# debugging_board_3_H-bridges.net
KiCad netlist of a schematic drawn in Altium Designer
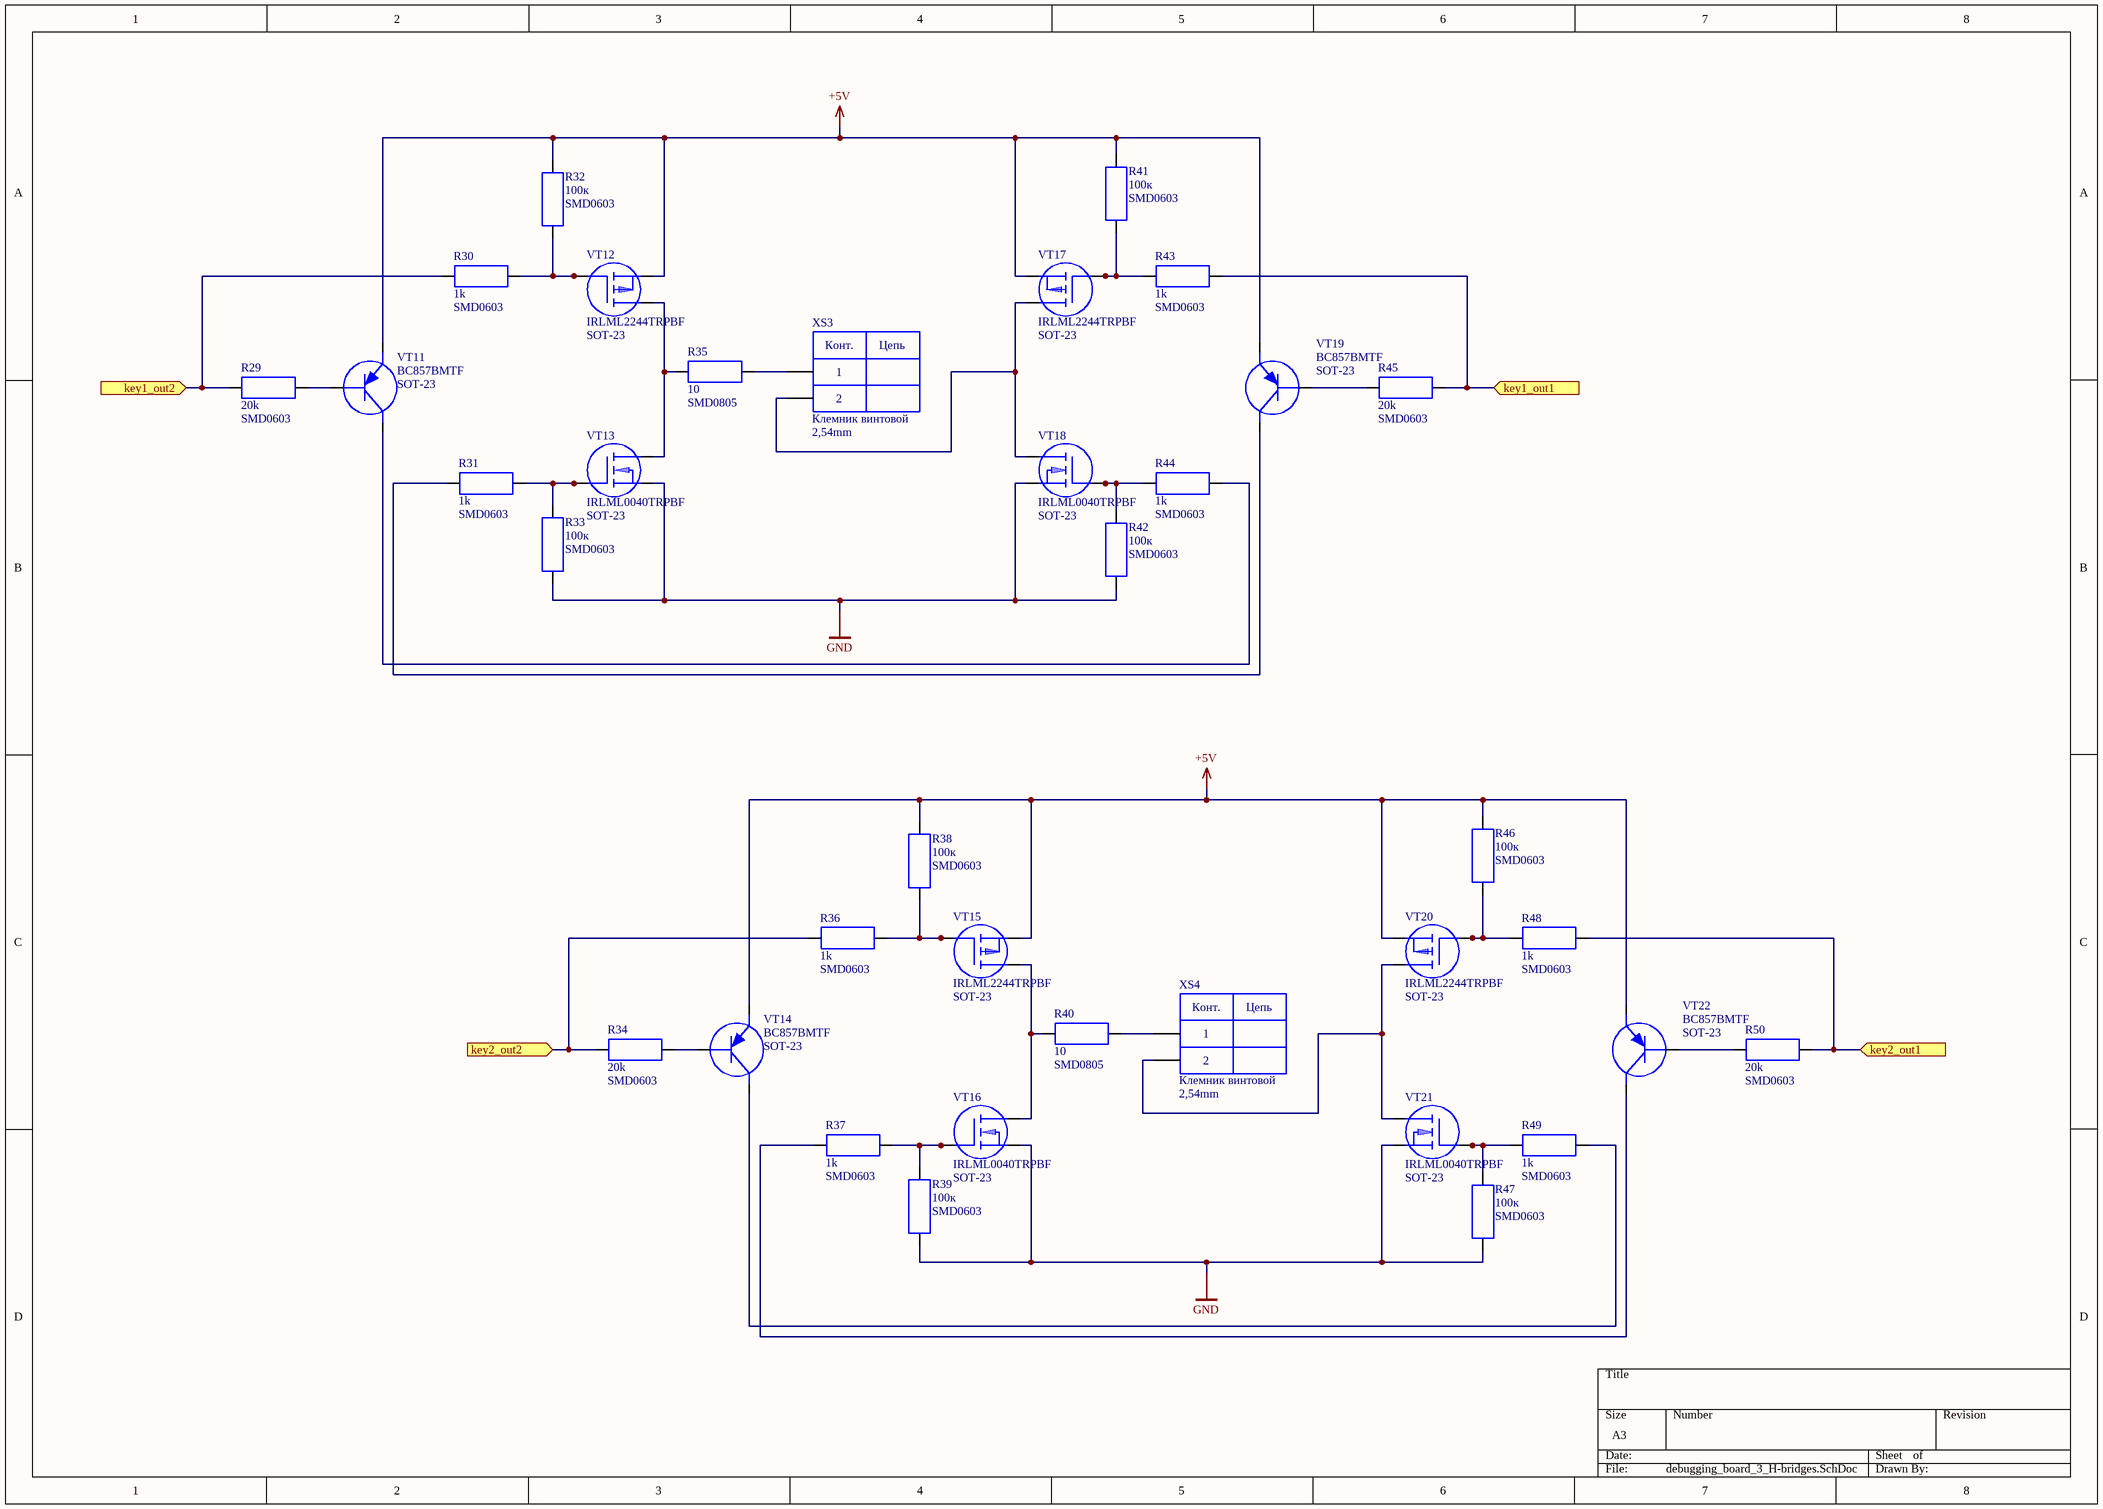
[diagram p0: debugging_board_3_H-bridges.SchDoc]

(export (version "E")
  (design (tool "Eeschema 10.0.6"))
  (components
    (comp (ref "R29")
      (value "20k")
      (footprint "SMD0603(1005)")
      (fields (field (name "PACKAGE") "SMD0603"))
      (libsource (lib "MechanikLibrary") (part "R_0603"))
    )
    (comp (ref "R30")
      (value "1k")
      (footprint "SMD0603(1005)")
      (fields (field (name "PACKAGE") "SMD0603"))
      (libsource (lib "MechanikLibrary") (part "R_0603"))
    )
    (comp (ref "R31")
      (value "1k")
      (footprint "SMD0603(1005)")
      (fields (field (name "PACKAGE") "SMD0603"))
      (libsource (lib "MechanikLibrary") (part "R_0603"))
    )
    (comp (ref "R32")
      (value "100к")
      (footprint "SMD0603(1005)")
      (fields (field (name "PACKAGE") "SMD0603"))
      (libsource (lib "MechanikLibrary") (part "R_0603"))
    )
    (comp (ref "R33")
      (value "100к")
      (footprint "SMD0603(1005)")
      (fields (field (name "PACKAGE") "SMD0603"))
      (libsource (lib "MechanikLibrary") (part "R_0603"))
    )
    (comp (ref "R34")
      (value "20k")
      (footprint "SMD0603(1005)")
      (fields (field (name "PACKAGE") "SMD0603"))
      (libsource (lib "MechanikLibrary") (part "R_0603"))
    )
    (comp (ref "R35")
      (value "10")
      (footprint "SMD0805(2012)")
      (fields (field (name "PACKAGE") "SMD0805"))
      (libsource (lib "MechanikLibrary") (part "R_0805"))
    )
    (comp (ref "R36")
      (value "1k")
      (footprint "SMD0603(1005)")
      (fields (field (name "PACKAGE") "SMD0603"))
      (libsource (lib "MechanikLibrary") (part "R_0603"))
    )
    (comp (ref "R37")
      (value "1k")
      (footprint "SMD0603(1005)")
      (fields (field (name "PACKAGE") "SMD0603"))
      (libsource (lib "MechanikLibrary") (part "R_0603"))
    )
    (comp (ref "R38")
      (value "100к")
      (footprint "SMD0603(1005)")
      (fields (field (name "PACKAGE") "SMD0603"))
      (libsource (lib "MechanikLibrary") (part "R_0603"))
    )
    (comp (ref "R39")
      (value "100к")
      (footprint "SMD0603(1005)")
      (fields (field (name "PACKAGE") "SMD0603"))
      (libsource (lib "MechanikLibrary") (part "R_0603"))
    )
    (comp (ref "R40")
      (value "10")
      (footprint "SMD0805(2012)")
      (fields (field (name "PACKAGE") "SMD0805"))
      (libsource (lib "MechanikLibrary") (part "R_0805"))
    )
    (comp (ref "R41")
      (value "100к")
      (footprint "SMD0603(1005)")
      (fields (field (name "PACKAGE") "SMD0603"))
      (libsource (lib "MechanikLibrary") (part "R_0603"))
    )
    (comp (ref "R42")
      (value "100к")
      (footprint "SMD0603(1005)")
      (fields (field (name "PACKAGE") "SMD0603"))
      (libsource (lib "MechanikLibrary") (part "R_0603"))
    )
    (comp (ref "R43")
      (value "1k")
      (footprint "SMD0603(1005)")
      (fields (field (name "PACKAGE") "SMD0603"))
      (libsource (lib "MechanikLibrary") (part "R_0603"))
    )
    (comp (ref "R44")
      (value "1k")
      (footprint "SMD0603(1005)")
      (fields (field (name "PACKAGE") "SMD0603"))
      (libsource (lib "MechanikLibrary") (part "R_0603"))
    )
    (comp (ref "R45")
      (value "20k")
      (footprint "SMD0603(1005)")
      (fields (field (name "PACKAGE") "SMD0603"))
      (libsource (lib "MechanikLibrary") (part "R_0603"))
    )
    (comp (ref "R46")
      (value "100к")
      (footprint "SMD0603(1005)")
      (fields (field (name "PACKAGE") "SMD0603"))
      (libsource (lib "MechanikLibrary") (part "R_0603"))
    )
    (comp (ref "R47")
      (value "100к")
      (footprint "SMD0603(1005)")
      (fields (field (name "PACKAGE") "SMD0603"))
      (libsource (lib "MechanikLibrary") (part "R_0603"))
    )
    (comp (ref "R48")
      (value "1k")
      (footprint "SMD0603(1005)")
      (fields (field (name "PACKAGE") "SMD0603"))
      (libsource (lib "MechanikLibrary") (part "R_0603"))
    )
    (comp (ref "R49")
      (value "1k")
      (footprint "SMD0603(1005)")
      (fields (field (name "PACKAGE") "SMD0603"))
      (libsource (lib "MechanikLibrary") (part "R_0603"))
    )
    (comp (ref "R50")
      (value "20k")
      (footprint "SMD0603(1005)")
      (fields (field (name "PACKAGE") "SMD0603"))
      (libsource (lib "MechanikLibrary") (part "R_0603"))
    )
    (comp (ref "VT11")
      (value "BC857BMTF")
      (footprint "SOT23-3")
      (fields (field (name "PACKAGE") "SOT-23"))
      (libsource (lib "MechanikLibrary") (part "VT_PNP_SOT23_3"))
    )
    (comp (ref "VT12")
      (value "IRLML2244TRPBF")
      (footprint "SOT23-3")
      (fields (field (name "PACKAGE") "SOT-23"))
      (libsource (lib "MechanikLibrary") (part "VT_P_MOSFET_SOT23_3"))
    )
    (comp (ref "VT13")
      (value "IRLML0040TRPBF")
      (footprint "SOT23-3")
      (fields (field (name "PACKAGE") "SOT-23"))
      (libsource (lib "MechanikLibrary") (part "VT_N_MOSFET_SOT23_3"))
    )
    (comp (ref "VT14")
      (value "BC857BMTF")
      (footprint "SOT23-3")
      (fields (field (name "PACKAGE") "SOT-23"))
      (libsource (lib "MechanikLibrary") (part "VT_PNP_SOT23_3"))
    )
    (comp (ref "VT15")
      (value "IRLML2244TRPBF")
      (footprint "SOT23-3")
      (fields (field (name "PACKAGE") "SOT-23"))
      (libsource (lib "MechanikLibrary") (part "VT_P_MOSFET_SOT23_3"))
    )
    (comp (ref "VT16")
      (value "IRLML0040TRPBF")
      (footprint "SOT23-3")
      (fields (field (name "PACKAGE") "SOT-23"))
      (libsource (lib "MechanikLibrary") (part "VT_N_MOSFET_SOT23_3"))
    )
    (comp (ref "VT17")
      (value "IRLML2244TRPBF")
      (footprint "SOT23-3")
      (fields (field (name "PACKAGE") "SOT-23"))
      (libsource (lib "MechanikLibrary") (part "VT_P_MOSFET_SOT23_3"))
    )
    (comp (ref "VT18")
      (value "IRLML0040TRPBF")
      (footprint "SOT23-3")
      (fields (field (name "PACKAGE") "SOT-23"))
      (libsource (lib "MechanikLibrary") (part "VT_N_MOSFET_SOT23_3"))
    )
    (comp (ref "VT19")
      (value "BC857BMTF")
      (footprint "SOT23-3")
      (fields (field (name "PACKAGE") "SOT-23"))
      (libsource (lib "MechanikLibrary") (part "VT_PNP_SOT23_3"))
    )
    (comp (ref "VT20")
      (value "IRLML2244TRPBF")
      (footprint "SOT23-3")
      (fields (field (name "PACKAGE") "SOT-23"))
      (libsource (lib "MechanikLibrary") (part "VT_P_MOSFET_SOT23_3"))
    )
    (comp (ref "VT21")
      (value "IRLML0040TRPBF")
      (footprint "SOT23-3")
      (fields (field (name "PACKAGE") "SOT-23"))
      (libsource (lib "MechanikLibrary") (part "VT_N_MOSFET_SOT23_3"))
    )
    (comp (ref "VT22")
      (value "BC857BMTF")
      (footprint "SOT23-3")
      (fields (field (name "PACKAGE") "SOT-23"))
      (libsource (lib "MechanikLibrary") (part "VT_PNP_SOT23_3"))
    )
    (comp (ref "XS3")
      (value "Клемник винтовой")
      (footprint "XS_2x2.54MM")
      (fields (field (name "PACKAGE") "2,54mm"))
      (libsource (lib "MechanikLibrary") (part "Клемник винтовой 2-контактный, 2,54мм"))
    )
    (comp (ref "XS4")
      (value "Клемник винтовой")
      (footprint "XS_2x2.54MM")
      (fields (field (name "PACKAGE") "2,54mm"))
      (libsource (lib "MechanikLibrary") (part "Клемник винтовой 2-контактный, 2,54мм"))
    )
  )
  (nets
    (net (code "1") (name "+5V") (class "Default")
      (node (ref "R32") (pin "2") (pintype "passive"))
      (node (ref "R38") (pin "2") (pintype "passive"))
      (node (ref "R41") (pin "2") (pintype "passive"))
      (node (ref "R46") (pin "2") (pintype "passive"))
      (node (ref "VT11") (pin "2") (pintype "passive"))
      (node (ref "VT12") (pin "2") (pintype "passive"))
      (node (ref "VT14") (pin "2") (pintype "passive"))
      (node (ref "VT15") (pin "2") (pintype "passive"))
      (node (ref "VT17") (pin "2") (pintype "passive"))
      (node (ref "VT19") (pin "2") (pintype "passive"))
      (node (ref "VT20") (pin "2") (pintype "passive"))
      (node (ref "VT22") (pin "2") (pintype "passive"))
    )
    (net (code "2") (name "/key1_out1") (class "Default")
      (node (ref "R43") (pin "1") (pintype "passive"))
      (node (ref "R45") (pin "2") (pintype "passive"))
    )
    (net (code "3") (name "/key1_out2") (class "Default")
      (node (ref "R29") (pin "1") (pintype "passive"))
      (node (ref "R30") (pin "2") (pintype "passive"))
    )
    (net (code "4") (name "/key2_out1") (class "Default")
      (node (ref "R48") (pin "1") (pintype "passive"))
      (node (ref "R50") (pin "2") (pintype "passive"))
    )
    (net (code "5") (name "/key2_out2") (class "Default")
      (node (ref "R34") (pin "1") (pintype "passive"))
      (node (ref "R36") (pin "2") (pintype "passive"))
    )
    (net (code "6") (name "GND") (class "Default")
      (node (ref "R33") (pin "1") (pintype "passive"))
      (node (ref "R39") (pin "1") (pintype "passive"))
      (node (ref "R42") (pin "1") (pintype "passive"))
      (node (ref "R47") (pin "1") (pintype "passive"))
      (node (ref "VT13") (pin "2") (pintype "passive"))
      (node (ref "VT16") (pin "2") (pintype "passive"))
      (node (ref "VT18") (pin "2") (pintype "passive"))
      (node (ref "VT21") (pin "2") (pintype "passive"))
    )
    (net (code "7") (name "Net-(R29-Pad2)") (class "Default")
      (node (ref "R29") (pin "2") (pintype "passive"))
      (node (ref "VT11") (pin "1") (pintype "passive"))
    )
    (net (code "8") (name "Net-(R30-Pad1)") (class "Default")
      (node (ref "R30") (pin "1") (pintype "passive"))
      (node (ref "R32") (pin "1") (pintype "passive"))
      (node (ref "VT12") (pin "1") (pintype "passive"))
    )
    (net (code "9") (name "Net-(R31-Pad1)") (class "Default")
      (node (ref "R31") (pin "1") (pintype "passive"))
      (node (ref "R33") (pin "2") (pintype "passive"))
      (node (ref "VT13") (pin "1") (pintype "passive"))
    )
    (net (code "10") (name "Net-(R31-Pad2)") (class "Default")
      (node (ref "R31") (pin "2") (pintype "passive"))
      (node (ref "VT19") (pin "3") (pintype "passive"))
    )
    (net (code "11") (name "Net-(R34-Pad2)") (class "Default")
      (node (ref "R34") (pin "2") (pintype "passive"))
      (node (ref "VT14") (pin "1") (pintype "passive"))
    )
    (net (code "12") (name "Net-(R35-Pad1)") (class "Default")
      (node (ref "R35") (pin "1") (pintype "passive"))
      (node (ref "XS3") (pin "1") (pintype "passive"))
    )
    (net (code "13") (name "Net-(R35-Pad2)") (class "Default")
      (node (ref "R35") (pin "2") (pintype "passive"))
      (node (ref "VT12") (pin "3") (pintype "passive"))
      (node (ref "VT13") (pin "3") (pintype "passive"))
    )
    (net (code "14") (name "Net-(R36-Pad1)") (class "Default")
      (node (ref "R36") (pin "1") (pintype "passive"))
      (node (ref "R38") (pin "1") (pintype "passive"))
      (node (ref "VT15") (pin "1") (pintype "passive"))
    )
    (net (code "15") (name "Net-(R37-Pad1)") (class "Default")
      (node (ref "R37") (pin "1") (pintype "passive"))
      (node (ref "R39") (pin "2") (pintype "passive"))
      (node (ref "VT16") (pin "1") (pintype "passive"))
    )
    (net (code "16") (name "Net-(R37-Pad2)") (class "Default")
      (node (ref "R37") (pin "2") (pintype "passive"))
      (node (ref "VT22") (pin "3") (pintype "passive"))
    )
    (net (code "17") (name "Net-(R40-Pad1)") (class "Default")
      (node (ref "R40") (pin "1") (pintype "passive"))
      (node (ref "XS4") (pin "1") (pintype "passive"))
    )
    (net (code "18") (name "Net-(R40-Pad2)") (class "Default")
      (node (ref "R40") (pin "2") (pintype "passive"))
      (node (ref "VT15") (pin "3") (pintype "passive"))
      (node (ref "VT16") (pin "3") (pintype "passive"))
    )
    (net (code "19") (name "Net-(R41-Pad1)") (class "Default")
      (node (ref "R41") (pin "1") (pintype "passive"))
      (node (ref "R43") (pin "2") (pintype "passive"))
      (node (ref "VT17") (pin "1") (pintype "passive"))
    )
    (net (code "20") (name "Net-(R42-Pad2)") (class "Default")
      (node (ref "R42") (pin "2") (pintype "passive"))
      (node (ref "R44") (pin "2") (pintype "passive"))
      (node (ref "VT18") (pin "1") (pintype "passive"))
    )
    (net (code "21") (name "Net-(R44-Pad1)") (class "Default")
      (node (ref "R44") (pin "1") (pintype "passive"))
      (node (ref "VT11") (pin "3") (pintype "passive"))
    )
    (net (code "22") (name "Net-(R45-Pad1)") (class "Default")
      (node (ref "R45") (pin "1") (pintype "passive"))
      (node (ref "VT19") (pin "1") (pintype "passive"))
    )
    (net (code "23") (name "Net-(R46-Pad1)") (class "Default")
      (node (ref "R46") (pin "1") (pintype "passive"))
      (node (ref "R48") (pin "2") (pintype "passive"))
      (node (ref "VT20") (pin "1") (pintype "passive"))
    )
    (net (code "24") (name "Net-(R47-Pad2)") (class "Default")
      (node (ref "R47") (pin "2") (pintype "passive"))
      (node (ref "R49") (pin "2") (pintype "passive"))
      (node (ref "VT21") (pin "1") (pintype "passive"))
    )
    (net (code "25") (name "Net-(R49-Pad1)") (class "Default")
      (node (ref "R49") (pin "1") (pintype "passive"))
      (node (ref "VT14") (pin "3") (pintype "passive"))
    )
    (net (code "26") (name "Net-(R50-Pad1)") (class "Default")
      (node (ref "R50") (pin "1") (pintype "passive"))
      (node (ref "VT22") (pin "1") (pintype "passive"))
    )
    (net (code "27") (name "Net-(VT17-Pad3)") (class "Default")
      (node (ref "VT17") (pin "3") (pintype "passive"))
      (node (ref "VT18") (pin "3") (pintype "passive"))
      (node (ref "XS3") (pin "2") (pintype "passive"))
    )
    (net (code "28") (name "Net-(VT20-Pad3)") (class "Default")
      (node (ref "VT20") (pin "3") (pintype "passive"))
      (node (ref "VT21") (pin "3") (pintype "passive"))
      (node (ref "XS4") (pin "2") (pintype "passive"))
    )
  )
)
